# MiniBoard.net
KiCad netlist of a schematic drawn in EAGLE
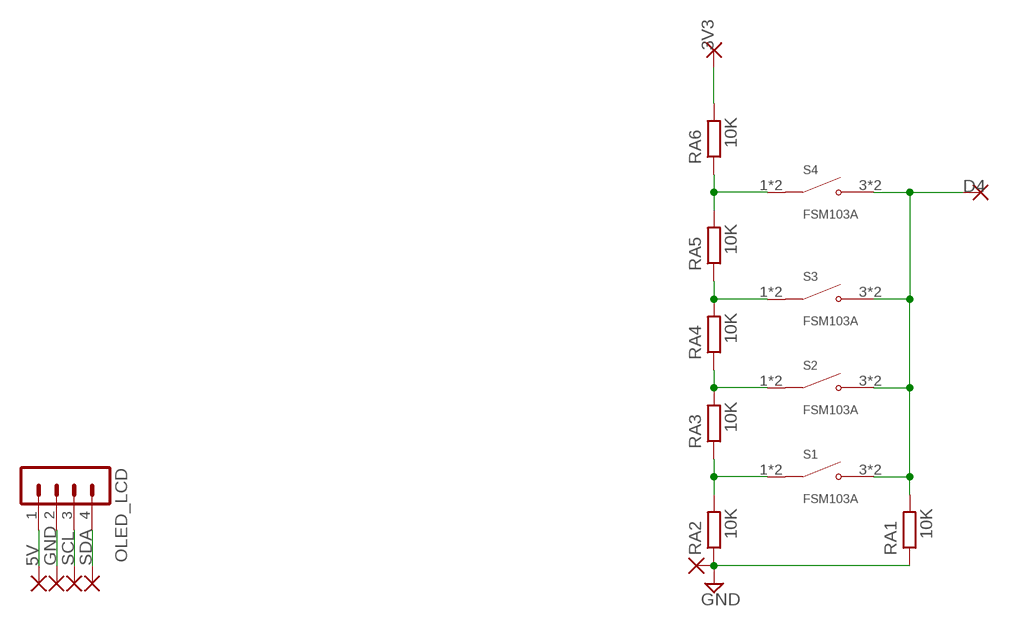
[diagram p0: schematic, sheet 1]

(export (version "E")
  (design (tool "Eeschema 10.0.6"))
  (components
    (comp (ref "OLED_LCD")
      (value "MA04-1")
      (footprint "eagle-import:MA04-1")
      (libsource (lib "eagle-import") (part "MA04-1"))
    )
    (comp (ref "PAD1")
      (value "WIREPAD1,6/0,9")
      (footprint "eagle-import:1,6_0,9")
      (libsource (lib "eagle-import") (part "WIREPAD1,6/0,9"))
    )
    (comp (ref "PAD25")
      (value "WIREPAD1,6/0,9")
      (footprint "eagle-import:1,6_0,9")
      (libsource (lib "eagle-import") (part "WIREPAD1,6/0,9"))
    )
    (comp (ref "PAD26")
      (value "WIREPAD1,6/0,9")
      (footprint "eagle-import:1,6_0,9")
      (libsource (lib "eagle-import") (part "WIREPAD1,6/0,9"))
    )
    (comp (ref "PAD52")
      (value "WIREPAD1,6/0,9")
      (footprint "eagle-import:1,6_0,9")
      (libsource (lib "eagle-import") (part "WIREPAD1,6/0,9"))
    )
    (comp (ref "PAD78")
      (value "WIREPAD1,6/0,9")
      (footprint "eagle-import:1,6_0,9")
      (libsource (lib "eagle-import") (part "WIREPAD1,6/0,9"))
    )
    (comp (ref "PAD103")
      (value "WIREPAD1,6/0,9")
      (footprint "eagle-import:1,6_0,9")
      (libsource (lib "eagle-import") (part "WIREPAD1,6/0,9"))
    )
    (comp (ref "PAD104")
      (value "WIREPAD1,6/0,9")
      (footprint "eagle-import:1,6_0,9")
      (libsource (lib "eagle-import") (part "WIREPAD1,6/0,9"))
    )
    (comp (ref "RA1")
      (value "10K")
      (footprint "eagle-import:0309_12")
      (libsource (lib "eagle-import") (part "R-EU_0309/12"))
    )
    (comp (ref "RA2")
      (value "10K")
      (footprint "eagle-import:0309_12")
      (libsource (lib "eagle-import") (part "R-EU_0309/12"))
    )
    (comp (ref "RA3")
      (value "10K")
      (footprint "eagle-import:0309_12")
      (libsource (lib "eagle-import") (part "R-EU_0309/12"))
    )
    (comp (ref "RA4")
      (value "10K")
      (footprint "eagle-import:0309_12")
      (libsource (lib "eagle-import") (part "R-EU_0309/12"))
    )
    (comp (ref "RA5")
      (value "10K")
      (footprint "eagle-import:0309_12")
      (libsource (lib "eagle-import") (part "R-EU_0309/12"))
    )
    (comp (ref "RA6")
      (value "10K")
      (footprint "eagle-import:0309_12")
      (libsource (lib "eagle-import") (part "R-EU_0309/12"))
    )
    (comp (ref "S1")
      (value "FSM103A")
      (footprint "eagle-import:SW_1571627-1")
      (fields (field (name "COMMENT") "1571627-1") (field (name "MF") "TE Connectivity"))
      (libsource (lib "eagle-import") (part "FSM103A"))
    )
    (comp (ref "S2")
      (value "FSM103A")
      (footprint "eagle-import:SW_1571627-1")
      (fields (field (name "COMMENT") "1571627-1") (field (name "MF") "TE Connectivity"))
      (libsource (lib "eagle-import") (part "FSM103A"))
    )
    (comp (ref "S3")
      (value "FSM103A")
      (footprint "eagle-import:SW_1571627-1")
      (fields (field (name "COMMENT") "1571627-1") (field (name "MF") "TE Connectivity"))
      (libsource (lib "eagle-import") (part "FSM103A"))
    )
    (comp (ref "S4")
      (value "FSM103A")
      (footprint "eagle-import:SW_1571627-1")
      (fields (field (name "COMMENT") "1571627-1") (field (name "MF") "TE Connectivity"))
      (libsource (lib "eagle-import") (part "FSM103A"))
    )
  )
  (nets
    (net (code "1") (name "/3V3") (class "Default")
      (node (ref "PAD104") (pin "1") (pinfunction "P_1") (pintype "passive"))
      (node (ref "RA6") (pin "2") (pinfunction "2_2") (pintype "passive"))
    )
    (net (code "2") (name "/5V") (class "Default")
      (node (ref "OLED_LCD") (pin "1") (pinfunction "1_1") (pintype "passive"))
      (node (ref "PAD25") (pin "1") (pinfunction "P_1") (pintype "passive"))
    )
    (net (code "3") (name "/D4") (class "Default")
      (node (ref "PAD103") (pin "1") (pinfunction "P_1") (pintype "passive"))
      (node (ref "RA1") (pin "2") (pinfunction "2_2") (pintype "passive"))
      (node (ref "S1") (pin "3") (pinfunction "NO_3") (pintype "passive"))
      (node (ref "S1") (pin "4") (pinfunction "NO_4") (pintype "passive"))
      (node (ref "S2") (pin "3") (pinfunction "NO_3") (pintype "passive"))
      (node (ref "S2") (pin "4") (pinfunction "NO_4") (pintype "passive"))
      (node (ref "S3") (pin "3") (pinfunction "NO_3") (pintype "passive"))
      (node (ref "S3") (pin "4") (pinfunction "NO_4") (pintype "passive"))
      (node (ref "S4") (pin "3") (pinfunction "NO_3") (pintype "passive"))
      (node (ref "S4") (pin "4") (pinfunction "NO_4") (pintype "passive"))
    )
    (net (code "4") (name "/SCL") (class "Default")
      (node (ref "OLED_LCD") (pin "3") (pinfunction "3_3") (pintype "passive"))
      (node (ref "PAD52") (pin "1") (pinfunction "P_1") (pintype "passive"))
    )
    (net (code "5") (name "/SDA") (class "Default")
      (node (ref "OLED_LCD") (pin "4") (pinfunction "4_4") (pintype "passive"))
      (node (ref "PAD78") (pin "1") (pinfunction "P_1") (pintype "passive"))
    )
    (net (code "6") (name "GND") (class "Default")
      (node (ref "OLED_LCD") (pin "2") (pinfunction "2_2") (pintype "passive"))
      (node (ref "PAD1") (pin "1") (pinfunction "P_1") (pintype "passive"))
      (node (ref "PAD26") (pin "1") (pinfunction "P_1") (pintype "passive"))
      (node (ref "RA1") (pin "1") (pinfunction "1_1") (pintype "passive"))
      (node (ref "RA2") (pin "1") (pinfunction "1_1") (pintype "passive"))
    )
    (net (code "7") (name "Net-(RA2-Pad2)") (class "Default")
      (node (ref "RA2") (pin "2") (pinfunction "2_2") (pintype "passive"))
      (node (ref "RA3") (pin "1") (pinfunction "1_1") (pintype "passive"))
      (node (ref "S1") (pin "1") (pinfunction "COM_1") (pintype "passive"))
      (node (ref "S1") (pin "2") (pinfunction "COM_2") (pintype "passive"))
    )
    (net (code "8") (name "Net-(RA3-Pad2)") (class "Default")
      (node (ref "RA3") (pin "2") (pinfunction "2_2") (pintype "passive"))
      (node (ref "RA4") (pin "1") (pinfunction "1_1") (pintype "passive"))
      (node (ref "S2") (pin "1") (pinfunction "COM_1") (pintype "passive"))
      (node (ref "S2") (pin "2") (pinfunction "COM_2") (pintype "passive"))
    )
    (net (code "9") (name "Net-(RA4-Pad2)") (class "Default")
      (node (ref "RA4") (pin "2") (pinfunction "2_2") (pintype "passive"))
      (node (ref "RA5") (pin "1") (pinfunction "1_1") (pintype "passive"))
      (node (ref "S3") (pin "1") (pinfunction "COM_1") (pintype "passive"))
      (node (ref "S3") (pin "2") (pinfunction "COM_2") (pintype "passive"))
    )
    (net (code "10") (name "Net-(RA5-Pad2)") (class "Default")
      (node (ref "RA5") (pin "2") (pinfunction "2_2") (pintype "passive"))
      (node (ref "RA6") (pin "1") (pinfunction "1_1") (pintype "passive"))
      (node (ref "S4") (pin "1") (pinfunction "COM_1") (pintype "passive"))
      (node (ref "S4") (pin "2") (pinfunction "COM_2") (pintype "passive"))
    )
  )
)
